# MOTOR_SIDE_PCB.net
KiCad netlist of a schematic drawn in EAGLE
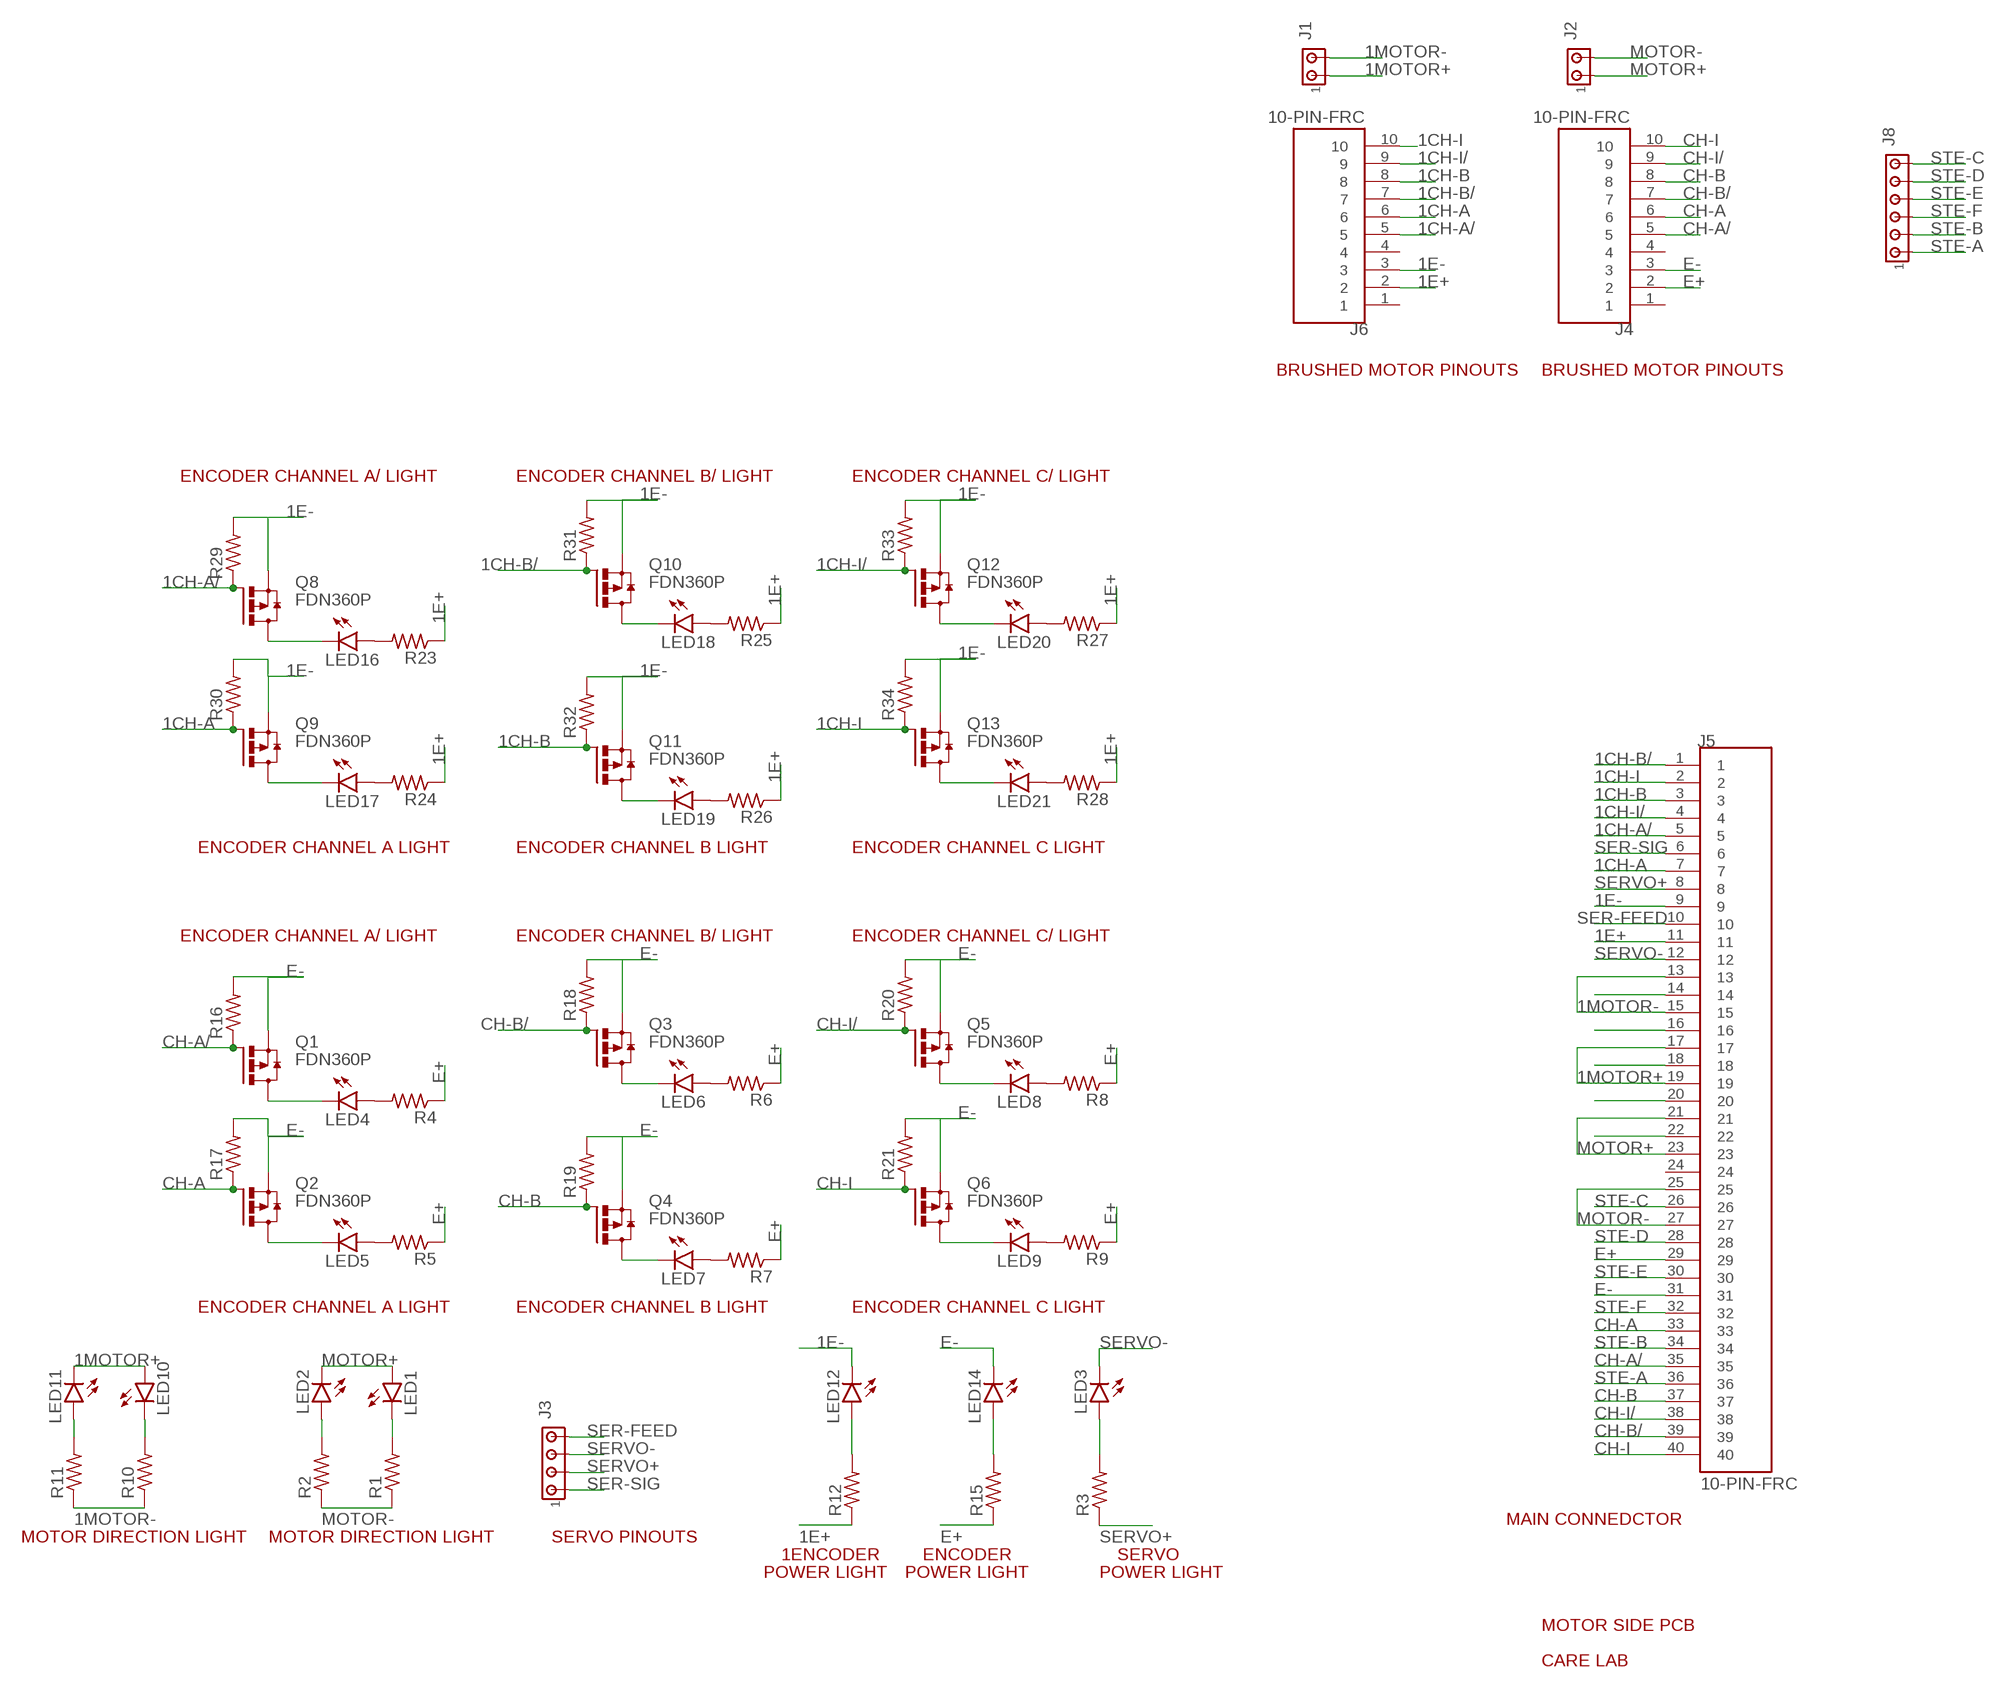
[diagram p0: schematic, sheet 1]

(export (version "E")
  (design (tool "Eeschema 10.0.6"))
  (components
    (comp (ref "J1")
      (value "MTA02-100")
      (footprint "eagle-import:10X02MTA")
      (libsource (lib "eagle-import") (part "MTA02-100"))
    )
    (comp (ref "J2")
      (value "MTA02-100")
      (footprint "eagle-import:10X02MTA")
      (libsource (lib "eagle-import") (part "MTA02-100"))
    )
    (comp (ref "J3")
      (value "MTA04-100")
      (footprint "eagle-import:10X04MTA")
      (libsource (lib "eagle-import") (part "MTA04-100"))
    )
    (comp (ref "J4")
      (value "10-PIN-FRC")
      (footprint "eagle-import:TE_2-1761603-3")
      (fields (field (name "COMMENT") "2-1761603-3") (field (name "MF") "TE Connectivity"))
      (libsource (lib "eagle-import") (part "10-PIN-FRC"))
    )
    (comp (ref "J5")
      (value "10-PIN-FRC")
      (footprint "eagle-import:TE_3-1761605-3")
      (fields (field (name "COMMENT") "3-1761605-3") (field (name "MF") "TE Connectivity"))
      (libsource (lib "eagle-import") (part "3-1761605-3_35747604_10-PIN-FRC"))
    )
    (comp (ref "J6")
      (value "10-PIN-FRC")
      (footprint "eagle-import:TE_2-1761603-3")
      (fields (field (name "COMMENT") "2-1761603-3") (field (name "MF") "TE Connectivity"))
      (libsource (lib "eagle-import") (part "10-PIN-FRC"))
    )
    (comp (ref "J8")
      (value "MTA06-100")
      (footprint "eagle-import:10X06MTA")
      (libsource (lib "eagle-import") (part "MTA06-100"))
    )
    (comp (ref "LED1")
      (value "LEDCHIP-LED0805")
      (footprint "eagle-import:CHIP-LED0805")
      (libsource (lib "eagle-import") (part "LEDCHIP-LED0805"))
    )
    (comp (ref "LED2")
      (value "LEDCHIP-LED0805")
      (footprint "eagle-import:CHIP-LED0805")
      (libsource (lib "eagle-import") (part "LEDCHIP-LED0805"))
    )
    (comp (ref "LED3")
      (value "LEDCHIP-LED0805")
      (footprint "eagle-import:CHIP-LED0805")
      (libsource (lib "eagle-import") (part "LEDCHIP-LED0805"))
    )
    (comp (ref "LED4")
      (value "LEDCHIP-LED0805")
      (footprint "eagle-import:CHIP-LED0805")
      (libsource (lib "eagle-import") (part "LEDCHIP-LED0805"))
    )
    (comp (ref "LED5")
      (value "LEDCHIP-LED0805")
      (footprint "eagle-import:CHIP-LED0805")
      (libsource (lib "eagle-import") (part "LEDCHIP-LED0805"))
    )
    (comp (ref "LED6")
      (value "LEDCHIP-LED0805")
      (footprint "eagle-import:CHIP-LED0805")
      (libsource (lib "eagle-import") (part "LEDCHIP-LED0805"))
    )
    (comp (ref "LED7")
      (value "LEDCHIP-LED0805")
      (footprint "eagle-import:CHIP-LED0805")
      (libsource (lib "eagle-import") (part "LEDCHIP-LED0805"))
    )
    (comp (ref "LED8")
      (value "LEDCHIP-LED0805")
      (footprint "eagle-import:CHIP-LED0805")
      (libsource (lib "eagle-import") (part "LEDCHIP-LED0805"))
    )
    (comp (ref "LED9")
      (value "LEDCHIP-LED0805")
      (footprint "eagle-import:CHIP-LED0805")
      (libsource (lib "eagle-import") (part "LEDCHIP-LED0805"))
    )
    (comp (ref "LED10")
      (value "LEDCHIP-LED0805")
      (footprint "eagle-import:CHIP-LED0805")
      (libsource (lib "eagle-import") (part "LEDCHIP-LED0805"))
    )
    (comp (ref "LED11")
      (value "LEDCHIP-LED0805")
      (footprint "eagle-import:CHIP-LED0805")
      (libsource (lib "eagle-import") (part "LEDCHIP-LED0805"))
    )
    (comp (ref "LED12")
      (value "LEDCHIP-LED0805")
      (footprint "eagle-import:CHIP-LED0805")
      (libsource (lib "eagle-import") (part "LEDCHIP-LED0805"))
    )
    (comp (ref "LED14")
      (value "LEDCHIP-LED0805")
      (footprint "eagle-import:CHIP-LED0805")
      (libsource (lib "eagle-import") (part "LEDCHIP-LED0805"))
    )
    (comp (ref "LED16")
      (value "LEDCHIP-LED0805")
      (footprint "eagle-import:CHIP-LED0805")
      (libsource (lib "eagle-import") (part "LEDCHIP-LED0805"))
    )
    (comp (ref "LED17")
      (value "LEDCHIP-LED0805")
      (footprint "eagle-import:CHIP-LED0805")
      (libsource (lib "eagle-import") (part "LEDCHIP-LED0805"))
    )
    (comp (ref "LED18")
      (value "LEDCHIP-LED0805")
      (footprint "eagle-import:CHIP-LED0805")
      (libsource (lib "eagle-import") (part "LEDCHIP-LED0805"))
    )
    (comp (ref "LED19")
      (value "LEDCHIP-LED0805")
      (footprint "eagle-import:CHIP-LED0805")
      (libsource (lib "eagle-import") (part "LEDCHIP-LED0805"))
    )
    (comp (ref "LED20")
      (value "LEDCHIP-LED0805")
      (footprint "eagle-import:CHIP-LED0805")
      (libsource (lib "eagle-import") (part "LEDCHIP-LED0805"))
    )
    (comp (ref "LED21")
      (value "LEDCHIP-LED0805")
      (footprint "eagle-import:CHIP-LED0805")
      (libsource (lib "eagle-import") (part "LEDCHIP-LED0805"))
    )
    (comp (ref "Q1")
      (value "FDN360P")
      (footprint "eagle-import:SUPER-SOT3")
      (libsource (lib "eagle-import") (part "FDN360P"))
    )
    (comp (ref "Q2")
      (value "FDN360P")
      (footprint "eagle-import:SUPER-SOT3")
      (libsource (lib "eagle-import") (part "FDN360P"))
    )
    (comp (ref "Q3")
      (value "FDN360P")
      (footprint "eagle-import:SUPER-SOT3")
      (libsource (lib "eagle-import") (part "FDN360P"))
    )
    (comp (ref "Q4")
      (value "FDN360P")
      (footprint "eagle-import:SUPER-SOT3")
      (libsource (lib "eagle-import") (part "FDN360P"))
    )
    (comp (ref "Q5")
      (value "FDN360P")
      (footprint "eagle-import:SUPER-SOT3")
      (libsource (lib "eagle-import") (part "FDN360P"))
    )
    (comp (ref "Q6")
      (value "FDN360P")
      (footprint "eagle-import:SUPER-SOT3")
      (libsource (lib "eagle-import") (part "FDN360P"))
    )
    (comp (ref "Q8")
      (value "FDN360P")
      (footprint "eagle-import:SUPER-SOT3")
      (libsource (lib "eagle-import") (part "FDN360P"))
    )
    (comp (ref "Q9")
      (value "FDN360P")
      (footprint "eagle-import:SUPER-SOT3")
      (libsource (lib "eagle-import") (part "FDN360P"))
    )
    (comp (ref "Q10")
      (value "FDN360P")
      (footprint "eagle-import:SUPER-SOT3")
      (libsource (lib "eagle-import") (part "FDN360P"))
    )
    (comp (ref "Q11")
      (value "FDN360P")
      (footprint "eagle-import:SUPER-SOT3")
      (libsource (lib "eagle-import") (part "FDN360P"))
    )
    (comp (ref "Q12")
      (value "FDN360P")
      (footprint "eagle-import:SUPER-SOT3")
      (libsource (lib "eagle-import") (part "FDN360P"))
    )
    (comp (ref "Q13")
      (value "FDN360P")
      (footprint "eagle-import:SUPER-SOT3")
      (libsource (lib "eagle-import") (part "FDN360P"))
    )
    (comp (ref "R1")
      (value "R-US_R0603")
      (footprint "eagle-import:R0603")
      (libsource (lib "eagle-import") (part "R-US_R0603"))
    )
    (comp (ref "R2")
      (value "R-US_R0603")
      (footprint "eagle-import:R0603")
      (libsource (lib "eagle-import") (part "R-US_R0603"))
    )
    (comp (ref "R3")
      (value "R-US_R0603")
      (footprint "eagle-import:R0603")
      (libsource (lib "eagle-import") (part "R-US_R0603"))
    )
    (comp (ref "R4")
      (value "R-US_R0603")
      (footprint "eagle-import:R0603")
      (libsource (lib "eagle-import") (part "R-US_R0603"))
    )
    (comp (ref "R5")
      (value "R-US_R0603")
      (footprint "eagle-import:R0603")
      (libsource (lib "eagle-import") (part "R-US_R0603"))
    )
    (comp (ref "R6")
      (value "R-US_R0603")
      (footprint "eagle-import:R0603")
      (libsource (lib "eagle-import") (part "R-US_R0603"))
    )
    (comp (ref "R7")
      (value "R-US_R0603")
      (footprint "eagle-import:R0603")
      (libsource (lib "eagle-import") (part "R-US_R0603"))
    )
    (comp (ref "R8")
      (value "R-US_R0603")
      (footprint "eagle-import:R0603")
      (libsource (lib "eagle-import") (part "R-US_R0603"))
    )
    (comp (ref "R9")
      (value "R-US_R0603")
      (footprint "eagle-import:R0603")
      (libsource (lib "eagle-import") (part "R-US_R0603"))
    )
    (comp (ref "R10")
      (value "R-US_R0603")
      (footprint "eagle-import:R0603")
      (libsource (lib "eagle-import") (part "R-US_R0603"))
    )
    (comp (ref "R11")
      (value "R-US_R0603")
      (footprint "eagle-import:R0603")
      (libsource (lib "eagle-import") (part "R-US_R0603"))
    )
    (comp (ref "R12")
      (value "R-US_R0603")
      (footprint "eagle-import:R0603")
      (libsource (lib "eagle-import") (part "R-US_R0603"))
    )
    (comp (ref "R15")
      (value "R-US_R0603")
      (footprint "eagle-import:R0603")
      (libsource (lib "eagle-import") (part "R-US_R0603"))
    )
    (comp (ref "R16")
      (value "R-US_R0603")
      (footprint "eagle-import:R0603")
      (libsource (lib "eagle-import") (part "R-US_R0603"))
    )
    (comp (ref "R17")
      (value "R-US_R0603")
      (footprint "eagle-import:R0603")
      (libsource (lib "eagle-import") (part "R-US_R0603"))
    )
    (comp (ref "R18")
      (value "R-US_R0603")
      (footprint "eagle-import:R0603")
      (libsource (lib "eagle-import") (part "R-US_R0603"))
    )
    (comp (ref "R19")
      (value "R-US_R0603")
      (footprint "eagle-import:R0603")
      (libsource (lib "eagle-import") (part "R-US_R0603"))
    )
    (comp (ref "R20")
      (value "R-US_R0603")
      (footprint "eagle-import:R0603")
      (libsource (lib "eagle-import") (part "R-US_R0603"))
    )
    (comp (ref "R21")
      (value "R-US_R0603")
      (footprint "eagle-import:R0603")
      (libsource (lib "eagle-import") (part "R-US_R0603"))
    )
    (comp (ref "R23")
      (value "R-US_R0603")
      (footprint "eagle-import:R0603")
      (libsource (lib "eagle-import") (part "R-US_R0603"))
    )
    (comp (ref "R24")
      (value "R-US_R0603")
      (footprint "eagle-import:R0603")
      (libsource (lib "eagle-import") (part "R-US_R0603"))
    )
    (comp (ref "R25")
      (value "R-US_R0603")
      (footprint "eagle-import:R0603")
      (libsource (lib "eagle-import") (part "R-US_R0603"))
    )
    (comp (ref "R26")
      (value "R-US_R0603")
      (footprint "eagle-import:R0603")
      (libsource (lib "eagle-import") (part "R-US_R0603"))
    )
    (comp (ref "R27")
      (value "R-US_R0603")
      (footprint "eagle-import:R0603")
      (libsource (lib "eagle-import") (part "R-US_R0603"))
    )
    (comp (ref "R28")
      (value "R-US_R0603")
      (footprint "eagle-import:R0603")
      (libsource (lib "eagle-import") (part "R-US_R0603"))
    )
    (comp (ref "R29")
      (value "R-US_R0603")
      (footprint "eagle-import:R0603")
      (libsource (lib "eagle-import") (part "R-US_R0603"))
    )
    (comp (ref "R30")
      (value "R-US_R0603")
      (footprint "eagle-import:R0603")
      (libsource (lib "eagle-import") (part "R-US_R0603"))
    )
    (comp (ref "R31")
      (value "R-US_R0603")
      (footprint "eagle-import:R0603")
      (libsource (lib "eagle-import") (part "R-US_R0603"))
    )
    (comp (ref "R32")
      (value "R-US_R0603")
      (footprint "eagle-import:R0603")
      (libsource (lib "eagle-import") (part "R-US_R0603"))
    )
    (comp (ref "R33")
      (value "R-US_R0603")
      (footprint "eagle-import:R0603")
      (libsource (lib "eagle-import") (part "R-US_R0603"))
    )
    (comp (ref "R34")
      (value "R-US_R0603")
      (footprint "eagle-import:R0603")
      (libsource (lib "eagle-import") (part "R-US_R0603"))
    )
  )
  (nets
    (net (code "1") (name "/1CH-A") (class "Default")
      (node (ref "J5") (pin "7") (pinfunction "7_7") (pintype "passive"))
      (node (ref "J6") (pin "6") (pinfunction "6_6") (pintype "passive"))
      (node (ref "Q9") (pin "1") (pinfunction "G_1") (pintype "passive"))
      (node (ref "R30") (pin "1") (pinfunction "1_1") (pintype "passive"))
    )
    (net (code "2") (name "/1CH-A{slash}") (class "Default")
      (node (ref "J5") (pin "5") (pinfunction "5_5") (pintype "passive"))
      (node (ref "J6") (pin "5") (pinfunction "5_5") (pintype "passive"))
      (node (ref "Q8") (pin "1") (pinfunction "G_1") (pintype "passive"))
      (node (ref "R29") (pin "1") (pinfunction "1_1") (pintype "passive"))
    )
    (net (code "3") (name "/1CH-B") (class "Default")
      (node (ref "J5") (pin "3") (pinfunction "3_3") (pintype "passive"))
      (node (ref "J6") (pin "8") (pinfunction "8_8") (pintype "passive"))
      (node (ref "Q11") (pin "1") (pinfunction "G_1") (pintype "passive"))
      (node (ref "R32") (pin "1") (pinfunction "1_1") (pintype "passive"))
    )
    (net (code "4") (name "/1CH-B{slash}") (class "Default")
      (node (ref "J5") (pin "1") (pinfunction "1_1") (pintype "passive"))
      (node (ref "J6") (pin "7") (pinfunction "7_7") (pintype "passive"))
      (node (ref "Q10") (pin "1") (pinfunction "G_1") (pintype "passive"))
      (node (ref "R31") (pin "1") (pinfunction "1_1") (pintype "passive"))
    )
    (net (code "5") (name "/1CH-I") (class "Default")
      (node (ref "J5") (pin "2") (pinfunction "2_2") (pintype "passive"))
      (node (ref "J6") (pin "10") (pinfunction "10_10") (pintype "passive"))
      (node (ref "Q13") (pin "1") (pinfunction "G_1") (pintype "passive"))
      (node (ref "R34") (pin "1") (pinfunction "1_1") (pintype "passive"))
    )
    (net (code "6") (name "/1CH-I{slash}") (class "Default")
      (node (ref "J5") (pin "4") (pinfunction "4_4") (pintype "passive"))
      (node (ref "J6") (pin "9") (pinfunction "9_9") (pintype "passive"))
      (node (ref "Q12") (pin "1") (pinfunction "G_1") (pintype "passive"))
      (node (ref "R33") (pin "1") (pinfunction "1_1") (pintype "passive"))
    )
    (net (code "7") (name "/1E+") (class "Default")
      (node (ref "J5") (pin "11") (pinfunction "11_11") (pintype "passive"))
      (node (ref "J6") (pin "2") (pinfunction "2_2") (pintype "passive"))
      (node (ref "R12") (pin "1") (pinfunction "1_1") (pintype "passive"))
      (node (ref "R23") (pin "1") (pinfunction "1_1") (pintype "passive"))
      (node (ref "R24") (pin "1") (pinfunction "1_1") (pintype "passive"))
      (node (ref "R25") (pin "1") (pinfunction "1_1") (pintype "passive"))
      (node (ref "R26") (pin "1") (pinfunction "1_1") (pintype "passive"))
      (node (ref "R27") (pin "1") (pinfunction "1_1") (pintype "passive"))
      (node (ref "R28") (pin "1") (pinfunction "1_1") (pintype "passive"))
    )
    (net (code "8") (name "/1E-") (class "Default")
      (node (ref "J5") (pin "9") (pinfunction "9_9") (pintype "passive"))
      (node (ref "J6") (pin "3") (pinfunction "3_3") (pintype "passive"))
      (node (ref "LED12") (pin "C") (pinfunction "C_C") (pintype "passive"))
      (node (ref "Q10") (pin "2") (pinfunction "S_2") (pintype "passive"))
      (node (ref "Q11") (pin "2") (pinfunction "S_2") (pintype "passive"))
      (node (ref "Q12") (pin "2") (pinfunction "S_2") (pintype "passive"))
      (node (ref "Q13") (pin "2") (pinfunction "S_2") (pintype "passive"))
      (node (ref "Q8") (pin "2") (pinfunction "S_2") (pintype "passive"))
      (node (ref "Q9") (pin "2") (pinfunction "S_2") (pintype "passive"))
      (node (ref "R29") (pin "2") (pinfunction "2_2") (pintype "passive"))
      (node (ref "R30") (pin "2") (pinfunction "2_2") (pintype "passive"))
      (node (ref "R31") (pin "2") (pinfunction "2_2") (pintype "passive"))
      (node (ref "R32") (pin "2") (pinfunction "2_2") (pintype "passive"))
      (node (ref "R33") (pin "2") (pinfunction "2_2") (pintype "passive"))
      (node (ref "R34") (pin "2") (pinfunction "2_2") (pintype "passive"))
    )
    (net (code "9") (name "/1MOTOR+") (class "Default")
      (node (ref "J1") (pin "1") (pinfunction "1_1") (pintype "passive"))
      (node (ref "J5") (pin "17") (pinfunction "17_17") (pintype "passive"))
      (node (ref "J5") (pin "19") (pinfunction "19_19") (pintype "passive"))
      (node (ref "LED10") (pin "A") (pinfunction "A_A") (pintype "passive"))
      (node (ref "LED11") (pin "C") (pinfunction "C_C") (pintype "passive"))
    )
    (net (code "10") (name "/1MOTOR-") (class "Default")
      (node (ref "J1") (pin "2") (pinfunction "2_2") (pintype "passive"))
      (node (ref "J5") (pin "13") (pinfunction "13_13") (pintype "passive"))
      (node (ref "J5") (pin "15") (pinfunction "15_15") (pintype "passive"))
      (node (ref "R10") (pin "1") (pinfunction "1_1") (pintype "passive"))
      (node (ref "R11") (pin "1") (pinfunction "1_1") (pintype "passive"))
    )
    (net (code "11") (name "/CH-A") (class "Default")
      (node (ref "J4") (pin "6") (pinfunction "6_6") (pintype "passive"))
      (node (ref "J5") (pin "33") (pinfunction "33_33") (pintype "passive"))
      (node (ref "Q2") (pin "1") (pinfunction "G_1") (pintype "passive"))
      (node (ref "R17") (pin "1") (pinfunction "1_1") (pintype "passive"))
    )
    (net (code "12") (name "/CH-A{slash}") (class "Default")
      (node (ref "J4") (pin "5") (pinfunction "5_5") (pintype "passive"))
      (node (ref "J5") (pin "35") (pinfunction "35_35") (pintype "passive"))
      (node (ref "Q1") (pin "1") (pinfunction "G_1") (pintype "passive"))
      (node (ref "R16") (pin "1") (pinfunction "1_1") (pintype "passive"))
    )
    (net (code "13") (name "/CH-B") (class "Default")
      (node (ref "J4") (pin "8") (pinfunction "8_8") (pintype "passive"))
      (node (ref "J5") (pin "37") (pinfunction "37_37") (pintype "passive"))
      (node (ref "Q4") (pin "1") (pinfunction "G_1") (pintype "passive"))
      (node (ref "R19") (pin "1") (pinfunction "1_1") (pintype "passive"))
    )
    (net (code "14") (name "/CH-B{slash}") (class "Default")
      (node (ref "J4") (pin "7") (pinfunction "7_7") (pintype "passive"))
      (node (ref "J5") (pin "39") (pinfunction "39_39") (pintype "passive"))
      (node (ref "Q3") (pin "1") (pinfunction "G_1") (pintype "passive"))
      (node (ref "R18") (pin "1") (pinfunction "1_1") (pintype "passive"))
    )
    (net (code "15") (name "/CH-I") (class "Default")
      (node (ref "J4") (pin "10") (pinfunction "10_10") (pintype "passive"))
      (node (ref "J5") (pin "40") (pinfunction "40_40") (pintype "passive"))
      (node (ref "Q6") (pin "1") (pinfunction "G_1") (pintype "passive"))
      (node (ref "R21") (pin "1") (pinfunction "1_1") (pintype "passive"))
    )
    (net (code "16") (name "/CH-I{slash}") (class "Default")
      (node (ref "J4") (pin "9") (pinfunction "9_9") (pintype "passive"))
      (node (ref "J5") (pin "38") (pinfunction "38_38") (pintype "passive"))
      (node (ref "Q5") (pin "1") (pinfunction "G_1") (pintype "passive"))
      (node (ref "R20") (pin "1") (pinfunction "1_1") (pintype "passive"))
    )
    (net (code "17") (name "/E+") (class "Default")
      (node (ref "J4") (pin "2") (pinfunction "2_2") (pintype "passive"))
      (node (ref "J5") (pin "29") (pinfunction "29_29") (pintype "passive"))
      (node (ref "R15") (pin "1") (pinfunction "1_1") (pintype "passive"))
      (node (ref "R4") (pin "1") (pinfunction "1_1") (pintype "passive"))
      (node (ref "R5") (pin "1") (pinfunction "1_1") (pintype "passive"))
      (node (ref "R6") (pin "1") (pinfunction "1_1") (pintype "passive"))
      (node (ref "R7") (pin "1") (pinfunction "1_1") (pintype "passive"))
      (node (ref "R8") (pin "1") (pinfunction "1_1") (pintype "passive"))
      (node (ref "R9") (pin "1") (pinfunction "1_1") (pintype "passive"))
    )
    (net (code "18") (name "/E-") (class "Default")
      (node (ref "J4") (pin "3") (pinfunction "3_3") (pintype "passive"))
      (node (ref "J5") (pin "31") (pinfunction "31_31") (pintype "passive"))
      (node (ref "LED14") (pin "C") (pinfunction "C_C") (pintype "passive"))
      (node (ref "Q1") (pin "2") (pinfunction "S_2") (pintype "passive"))
      (node (ref "Q2") (pin "2") (pinfunction "S_2") (pintype "passive"))
      (node (ref "Q3") (pin "2") (pinfunction "S_2") (pintype "passive"))
      (node (ref "Q4") (pin "2") (pinfunction "S_2") (pintype "passive"))
      (node (ref "Q5") (pin "2") (pinfunction "S_2") (pintype "passive"))
      (node (ref "Q6") (pin "2") (pinfunction "S_2") (pintype "passive"))
      (node (ref "R16") (pin "2") (pinfunction "2_2") (pintype "passive"))
      (node (ref "R17") (pin "2") (pinfunction "2_2") (pintype "passive"))
      (node (ref "R18") (pin "2") (pinfunction "2_2") (pintype "passive"))
      (node (ref "R19") (pin "2") (pinfunction "2_2") (pintype "passive"))
      (node (ref "R20") (pin "2") (pinfunction "2_2") (pintype "passive"))
      (node (ref "R21") (pin "2") (pinfunction "2_2") (pintype "passive"))
    )
    (net (code "19") (name "/MOTOR+") (class "Default")
      (node (ref "J2") (pin "1") (pinfunction "1_1") (pintype "passive"))
      (node (ref "J5") (pin "21") (pinfunction "21_21") (pintype "passive"))
      (node (ref "J5") (pin "23") (pinfunction "23_23") (pintype "passive"))
      (node (ref "LED1") (pin "A") (pinfunction "A_A") (pintype "passive"))
      (node (ref "LED2") (pin "C") (pinfunction "C_C") (pintype "passive"))
    )
    (net (code "20") (name "/MOTOR-") (class "Default")
      (node (ref "J2") (pin "2") (pinfunction "2_2") (pintype "passive"))
      (node (ref "J5") (pin "25") (pinfunction "25_25") (pintype "passive"))
      (node (ref "J5") (pin "27") (pinfunction "27_27") (pintype "passive"))
      (node (ref "R1") (pin "1") (pinfunction "1_1") (pintype "passive"))
      (node (ref "R2") (pin "1") (pinfunction "1_1") (pintype "passive"))
    )
    (net (code "21") (name "/SER-FEED") (class "Default")
      (node (ref "J3") (pin "4") (pinfunction "4_4") (pintype "passive"))
      (node (ref "J5") (pin "10") (pinfunction "10_10") (pintype "passive"))
    )
    (net (code "22") (name "/SER-SIG") (class "Default")
      (node (ref "J3") (pin "1") (pinfunction "1_1") (pintype "passive"))
      (node (ref "J5") (pin "6") (pinfunction "6_6") (pintype "passive"))
    )
    (net (code "23") (name "/SERVO+") (class "Default")
      (node (ref "J3") (pin "2") (pinfunction "2_2") (pintype "passive"))
      (node (ref "J5") (pin "8") (pinfunction "8_8") (pintype "passive"))
      (node (ref "R3") (pin "1") (pinfunction "1_1") (pintype "passive"))
    )
    (net (code "24") (name "/SERVO-") (class "Default")
      (node (ref "J3") (pin "3") (pinfunction "3_3") (pintype "passive"))
      (node (ref "J5") (pin "12") (pinfunction "12_12") (pintype "passive"))
      (node (ref "LED3") (pin "C") (pinfunction "C_C") (pintype "passive"))
    )
    (net (code "25") (name "/STE-A") (class "Default")
      (node (ref "J5") (pin "36") (pinfunction "36_36") (pintype "passive"))
      (node (ref "J8") (pin "1") (pinfunction "1_1") (pintype "passive"))
    )
    (net (code "26") (name "/STE-B") (class "Default")
      (node (ref "J5") (pin "34") (pinfunction "34_34") (pintype "passive"))
      (node (ref "J8") (pin "2") (pinfunction "2_2") (pintype "passive"))
    )
    (net (code "27") (name "/STE-C") (class "Default")
      (node (ref "J5") (pin "26") (pinfunction "26_26") (pintype "passive"))
      (node (ref "J8") (pin "6") (pinfunction "6_6") (pintype "passive"))
    )
    (net (code "28") (name "/STE-D") (class "Default")
      (node (ref "J5") (pin "28") (pinfunction "28_28") (pintype "passive"))
      (node (ref "J8") (pin "5") (pinfunction "5_5") (pintype "passive"))
    )
    (net (code "29") (name "/STE-E") (class "Default")
      (node (ref "J5") (pin "30") (pinfunction "30_30") (pintype "passive"))
      (node (ref "J8") (pin "4") (pinfunction "4_4") (pintype "passive"))
    )
    (net (code "30") (name "/STE-F") (class "Default")
      (node (ref "J5") (pin "32") (pinfunction "32_32") (pintype "passive"))
      (node (ref "J8") (pin "3") (pinfunction "3_3") (pintype "passive"))
    )
    (net (code "31") (name "Net-(LED1-PadC)") (class "Default")
      (node (ref "LED1") (pin "C") (pinfunction "C_C") (pintype "passive"))
      (node (ref "R1") (pin "2") (pinfunction "2_2") (pintype "passive"))
    )
    (net (code "32") (name "Net-(LED2-PadA)") (class "Default")
      (node (ref "LED2") (pin "A") (pinfunction "A_A") (pintype "passive"))
      (node (ref "R2") (pin "2") (pinfunction "2_2") (pintype "passive"))
    )
    (net (code "33") (name "Net-(LED3-PadA)") (class "Default")
      (node (ref "LED3") (pin "A") (pinfunction "A_A") (pintype "passive"))
      (node (ref "R3") (pin "2") (pinfunction "2_2") (pintype "passive"))
    )
    (net (code "34") (name "Net-(LED4-PadA)") (class "Default")
      (node (ref "LED4") (pin "A") (pinfunction "A_A") (pintype "passive"))
      (node (ref "R4") (pin "2") (pinfunction "2_2") (pintype "passive"))
    )
    (net (code "35") (name "Net-(LED5-PadA)") (class "Default")
      (node (ref "LED5") (pin "A") (pinfunction "A_A") (pintype "passive"))
      (node (ref "R5") (pin "2") (pinfunction "2_2") (pintype "passive"))
    )
    (net (code "36") (name "Net-(LED6-PadA)") (class "Default")
      (node (ref "LED6") (pin "A") (pinfunction "A_A") (pintype "passive"))
      (node (ref "R6") (pin "2") (pinfunction "2_2") (pintype "passive"))
    )
    (net (code "37") (name "Net-(LED7-PadA)") (class "Default")
      (node (ref "LED7") (pin "A") (pinfunction "A_A") (pintype "passive"))
      (node (ref "R7") (pin "2") (pinfunction "2_2") (pintype "passive"))
    )
    (net (code "38") (name "Net-(LED8-PadA)") (class "Default")
      (node (ref "LED8") (pin "A") (pinfunction "A_A") (pintype "passive"))
      (node (ref "R8") (pin "2") (pinfunction "2_2") (pintype "passive"))
    )
    (net (code "39") (name "Net-(LED9-PadA)") (class "Default")
      (node (ref "LED9") (pin "A") (pinfunction "A_A") (pintype "passive"))
      (node (ref "R9") (pin "2") (pinfunction "2_2") (pintype "passive"))
    )
    (net (code "40") (name "Net-(LED10-PadC)") (class "Default")
      (node (ref "LED10") (pin "C") (pinfunction "C_C") (pintype "passive"))
      (node (ref "R10") (pin "2") (pinfunction "2_2") (pintype "passive"))
    )
    (net (code "41") (name "Net-(LED11-PadA)") (class "Default")
      (node (ref "LED11") (pin "A") (pinfunction "A_A") (pintype "passive"))
      (node (ref "R11") (pin "2") (pinfunction "2_2") (pintype "passive"))
    )
    (net (code "42") (name "Net-(LED12-PadA)") (class "Default")
      (node (ref "LED12") (pin "A") (pinfunction "A_A") (pintype "passive"))
      (node (ref "R12") (pin "2") (pinfunction "2_2") (pintype "passive"))
    )
    (net (code "43") (name "Net-(LED14-PadA)") (class "Default")
      (node (ref "LED14") (pin "A") (pinfunction "A_A") (pintype "passive"))
      (node (ref "R15") (pin "2") (pinfunction "2_2") (pintype "passive"))
    )
    (net (code "44") (name "Net-(LED16-PadA)") (class "Default")
      (node (ref "LED16") (pin "A") (pinfunction "A_A") (pintype "passive"))
      (node (ref "R23") (pin "2") (pinfunction "2_2") (pintype "passive"))
    )
    (net (code "45") (name "Net-(LED17-PadA)") (class "Default")
      (node (ref "LED17") (pin "A") (pinfunction "A_A") (pintype "passive"))
      (node (ref "R24") (pin "2") (pinfunction "2_2") (pintype "passive"))
    )
    (net (code "46") (name "Net-(LED18-PadA)") (class "Default")
      (node (ref "LED18") (pin "A") (pinfunction "A_A") (pintype "passive"))
      (node (ref "R25") (pin "2") (pinfunction "2_2") (pintype "passive"))
    )
    (net (code "47") (name "Net-(LED19-PadA)") (class "Default")
      (node (ref "LED19") (pin "A") (pinfunction "A_A") (pintype "passive"))
      (node (ref "R26") (pin "2") (pinfunction "2_2") (pintype "passive"))
    )
    (net (code "48") (name "Net-(LED20-PadA)") (class "Default")
      (node (ref "LED20") (pin "A") (pinfunction "A_A") (pintype "passive"))
      (node (ref "R27") (pin "2") (pinfunction "2_2") (pintype "passive"))
    )
    (net (code "49") (name "Net-(LED21-PadA)") (class "Default")
      (node (ref "LED21") (pin "A") (pinfunction "A_A") (pintype "passive"))
      (node (ref "R28") (pin "2") (pinfunction "2_2") (pintype "passive"))
    )
    (net (code "50") (name "Net-(Q1-D)") (class "Default")
      (node (ref "LED4") (pin "C") (pinfunction "C_C") (pintype "passive"))
      (node (ref "Q1") (pin "3") (pinfunction "D_3") (pintype "passive"))
    )
    (net (code "51") (name "Net-(Q2-D)") (class "Default")
      (node (ref "LED5") (pin "C") (pinfunction "C_C") (pintype "passive"))
      (node (ref "Q2") (pin "3") (pinfunction "D_3") (pintype "passive"))
    )
    (net (code "52") (name "Net-(Q3-D)") (class "Default")
      (node (ref "LED6") (pin "C") (pinfunction "C_C") (pintype "passive"))
      (node (ref "Q3") (pin "3") (pinfunction "D_3") (pintype "passive"))
    )
    (net (code "53") (name "Net-(Q4-D)") (class "Default")
      (node (ref "LED7") (pin "C") (pinfunction "C_C") (pintype "passive"))
      (node (ref "Q4") (pin "3") (pinfunction "D_3") (pintype "passive"))
    )
    (net (code "54") (name "Net-(Q5-D)") (class "Default")
      (node (ref "LED8") (pin "C") (pinfunction "C_C") (pintype "passive"))
      (node (ref "Q5") (pin "3") (pinfunction "D_3") (pintype "passive"))
    )
    (net (code "55") (name "Net-(Q6-D)") (class "Default")
      (node (ref "LED9") (pin "C") (pinfunction "C_C") (pintype "passive"))
      (node (ref "Q6") (pin "3") (pinfunction "D_3") (pintype "passive"))
    )
    (net (code "56") (name "Net-(Q8-D)") (class "Default")
      (node (ref "LED16") (pin "C") (pinfunction "C_C") (pintype "passive"))
      (node (ref "Q8") (pin "3") (pinfunction "D_3") (pintype "passive"))
    )
    (net (code "57") (name "Net-(Q9-D)") (class "Default")
      (node (ref "LED17") (pin "C") (pinfunction "C_C") (pintype "passive"))
      (node (ref "Q9") (pin "3") (pinfunction "D_3") (pintype "passive"))
    )
    (net (code "58") (name "Net-(Q10-D)") (class "Default")
      (node (ref "LED18") (pin "C") (pinfunction "C_C") (pintype "passive"))
      (node (ref "Q10") (pin "3") (pinfunction "D_3") (pintype "passive"))
    )
    (net (code "59") (name "Net-(Q11-D)") (class "Default")
      (node (ref "LED19") (pin "C") (pinfunction "C_C") (pintype "passive"))
      (node (ref "Q11") (pin "3") (pinfunction "D_3") (pintype "passive"))
    )
    (net (code "60") (name "Net-(Q12-D)") (class "Default")
      (node (ref "LED20") (pin "C") (pinfunction "C_C") (pintype "passive"))
      (node (ref "Q12") (pin "3") (pinfunction "D_3") (pintype "passive"))
    )
    (net (code "61") (name "Net-(Q13-D)") (class "Default")
      (node (ref "LED21") (pin "C") (pinfunction "C_C") (pintype "passive"))
      (node (ref "Q13") (pin "3") (pinfunction "D_3") (pintype "passive"))
    )
    (net (code "62") (name "unconnected-(J4-Pad1)") (class "Default")
      (node (ref "J4") (pin "1") (pinfunction "1_1") (pintype "passive"))
    )
    (net (code "63") (name "unconnected-(J4-Pad4)") (class "Default")
      (node (ref "J4") (pin "4") (pinfunction "4_4") (pintype "passive"))
    )
    (net (code "64") (name "unconnected-(J5-Pad14)") (class "Default")
      (node (ref "J5") (pin "14") (pinfunction "14_14") (pintype "passive"))
    )
    (net (code "65") (name "unconnected-(J5-Pad16)") (class "Default")
      (node (ref "J5") (pin "16") (pinfunction "16_16") (pintype "passive"))
    )
    (net (code "66") (name "unconnected-(J5-Pad18)") (class "Default")
      (node (ref "J5") (pin "18") (pinfunction "18_18") (pintype "passive"))
    )
    (net (code "67") (name "unconnected-(J5-Pad20)") (class "Default")
      (node (ref "J5") (pin "20") (pinfunction "20_20") (pintype "passive"))
    )
    (net (code "68") (name "unconnected-(J5-Pad22)") (class "Default")
      (node (ref "J5") (pin "22") (pinfunction "22_22") (pintype "passive"))
    )
    (net (code "69") (name "unconnected-(J5-Pad24)") (class "Default")
      (node (ref "J5") (pin "24") (pinfunction "24_24") (pintype "passive"))
    )
    (net (code "70") (name "unconnected-(J6-Pad1)") (class "Default")
      (node (ref "J6") (pin "1") (pinfunction "1_1") (pintype "passive"))
    )
    (net (code "71") (name "unconnected-(J6-Pad4)") (class "Default")
      (node (ref "J6") (pin "4") (pinfunction "4_4") (pintype "passive"))
    )
  )
)
